# Sensors.net
KiCad netlist of a schematic drawn in Altium Designer
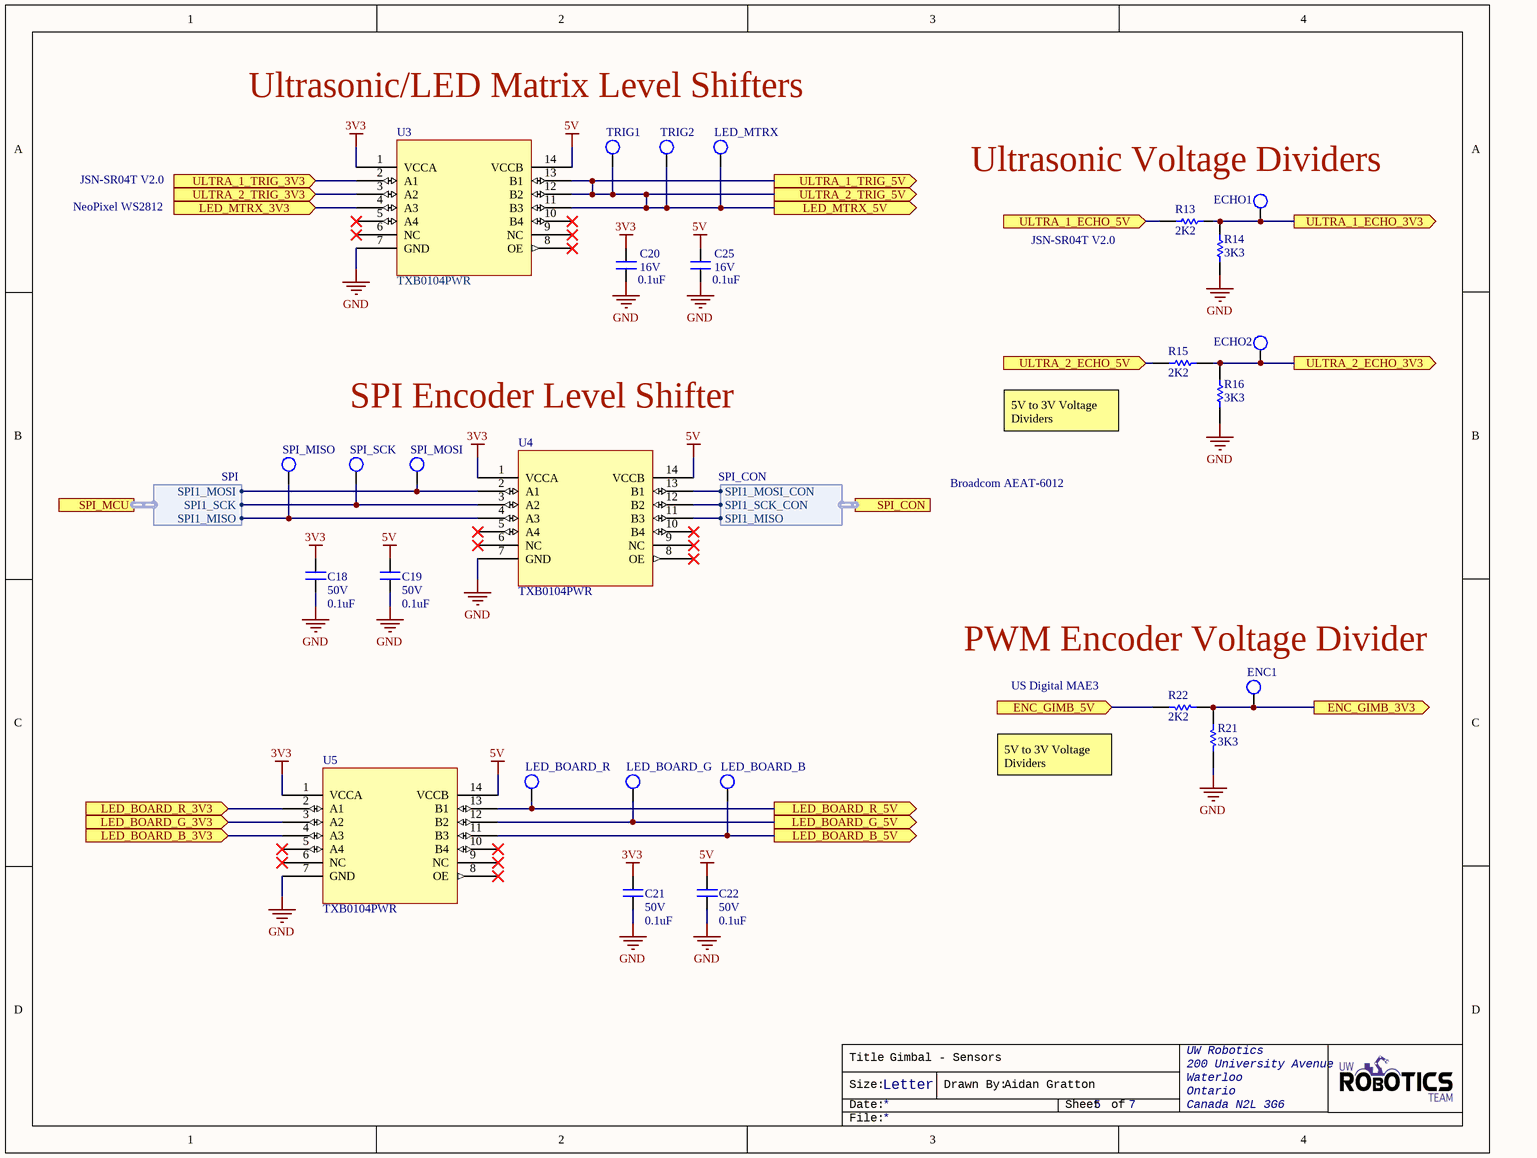
[diagram p0: Sensors.SchDoc]

(export (version "E")
  (design (tool "Eeschema 10.0.6"))
  (components
    (comp (ref "C18")
      (value "0.1uF")
      (footprint "CAPC0603(1608)55_N")
      (description "CAP CER 0.1UF 50V X7R 0603")
      (fields
        (field (name "MPN") "CC0603KRX7R9BB104")
        (field (name "MANUFACTURER") "Yageo")
        (field (name "VOLTAGE RATING") "50V")
      )
      (libsource (lib "UWRT_Schematic_Library_2020") (part "CAP_0.1uF_50V_0603"))
    )
    (comp (ref "C19")
      (value "0.1uF")
      (footprint "CAPC0603(1608)55_N")
      (description "CAP CER 0.1UF 50V X7R 0603")
      (fields
        (field (name "MPN") "CC0603KRX7R9BB104")
        (field (name "MANUFACTURER") "Yageo")
        (field (name "VOLTAGE RATING") "50V")
      )
      (libsource (lib "UWRT_Schematic_Library_2020") (part "CAP_0.1uF_50V_0603"))
    )
    (comp (ref "C20")
      (value "0.1uF")
      (footprint "CAPC0603(1608)55_N")
      (description "CAP CER 0.1UF 16V X7R 0603")
      (fields (field (name "VOLTAGE RATING") "16V") (field (name "Comment") "CAP_0.1uF_16V_0603"))
      (libsource (lib "UWRT_Schematic_Library_2020") (part "CAP_0.1uF_16V_0603"))
    )
    (comp (ref "C21")
      (value "0.1uF")
      (footprint "CAPC0603(1608)55_N")
      (description "CAP CER 0.1UF 50V X7R 0603")
      (fields
        (field (name "MPN") "CC0603KRX7R9BB104")
        (field (name "MANUFACTURER") "Yageo")
        (field (name "VOLTAGE RATING") "50V")
      )
      (libsource (lib "UWRT_Schematic_Library_2020") (part "CAP_0.1uF_50V_0603"))
    )
    (comp (ref "C22")
      (value "0.1uF")
      (footprint "CAPC0603(1608)55_N")
      (description "CAP CER 0.1UF 50V X7R 0603")
      (fields
        (field (name "MPN") "CC0603KRX7R9BB104")
        (field (name "MANUFACTURER") "Yageo")
        (field (name "VOLTAGE RATING") "50V")
      )
      (libsource (lib "UWRT_Schematic_Library_2020") (part "CAP_0.1uF_50V_0603"))
    )
    (comp (ref "C25")
      (value "0.1uF")
      (footprint "CAPC0603(1608)55_N")
      (description "CAP CER 0.1UF 16V X7R 0603")
      (fields (field (name "VOLTAGE RATING") "16V") (field (name "Comment") "CAP_0.1uF_16V_0603"))
      (libsource (lib "UWRT_Schematic_Library_2020") (part "CAP_0.1uF_16V_0603"))
    )
    (comp (ref "ECHO1")
      (value "TESTPOINT_LOOP")
      (footprint "TESTPOINT_LOOP")
      (description "Loop testpoint through-hole pad")
      (fields (field (name "MANUFACTURER") "Keystone Electronics"))
      (libsource (lib "UWRT_Schematic_Library_2020") (part "TESTPOINT_LOOP"))
    )
    (comp (ref "ECHO2")
      (value "TESTPOINT_LOOP")
      (footprint "TESTPOINT_LOOP")
      (description "Loop testpoint through-hole pad")
      (fields (field (name "MANUFACTURER") "Keystone Electronics"))
      (libsource (lib "UWRT_Schematic_Library_2020") (part "TESTPOINT_LOOP"))
    )
    (comp (ref "ENC1")
      (value "TESTPOINT_LOOP")
      (footprint "TESTPOINT_LOOP")
      (description "Loop testpoint through-hole pad")
      (fields (field (name "MANUFACTURER") "Keystone Electronics"))
      (libsource (lib "UWRT_Schematic_Library_2020") (part "TESTPOINT_LOOP"))
    )
    (comp (ref "LED_BOARD_B")
      (value "TESTPOINT_LOOP")
      (footprint "TESTPOINT_LOOP")
      (description "Loop testpoint through-hole pad")
      (fields (field (name "MANUFACTURER") "Keystone Electronics"))
      (libsource (lib "UWRT_Schematic_Library_2020") (part "TESTPOINT_LOOP"))
    )
    (comp (ref "LED_BOARD_G")
      (value "TESTPOINT_LOOP")
      (footprint "TESTPOINT_LOOP")
      (description "Loop testpoint through-hole pad")
      (fields (field (name "MANUFACTURER") "Keystone Electronics"))
      (libsource (lib "UWRT_Schematic_Library_2020") (part "TESTPOINT_LOOP"))
    )
    (comp (ref "LED_BOARD_R")
      (value "TESTPOINT_LOOP")
      (footprint "TESTPOINT_LOOP")
      (description "Loop testpoint through-hole pad")
      (fields (field (name "MANUFACTURER") "Keystone Electronics"))
      (libsource (lib "UWRT_Schematic_Library_2020") (part "TESTPOINT_LOOP"))
    )
    (comp (ref "LED_MTRX")
      (value "TESTPOINT_LOOP")
      (footprint "TESTPOINT_LOOP")
      (description "Loop testpoint through-hole pad")
      (libsource (lib "UWRT_Schematic_Library_2020") (part "TESTPOINT_LOOP"))
    )
    (comp (ref "R13")
      (value "2K2")
      (footprint "RESC0603(1608)_N")
      (description "RES SMD 2.2K OHM 1% 1/10W 0603")
      (fields (field (name "MANUFACTURER") "Yageo") (field (name "TOLERANCE") "1%"))
      (libsource (lib "UWRT_Schematic_Library_2020") (part "RES_2K2_0603"))
    )
    (comp (ref "R14")
      (value "3K3")
      (footprint "RESC0603(1608)_N")
      (description "RES SMD 3.3K OHM 5% 1/10W 0603")
      (fields (field (name "TOLERANCE") "5%") (field (name "DIGIKEY PART NUMBER") "311-3.3KGRCT-ND"))
      (libsource (lib "") (part "RES_3K3_0603_1"))
    )
    (comp (ref "R15")
      (value "2K2")
      (footprint "RESC0603(1608)_N")
      (description "RES SMD 2.2K OHM 1% 1/10W 0603")
      (fields (field (name "MANUFACTURER") "Yageo") (field (name "TOLERANCE") "1%"))
      (libsource (lib "UWRT_Schematic_Library_2020") (part "RES_2K2_0603"))
    )
    (comp (ref "R16")
      (value "3K3")
      (footprint "RESC0603(1608)_N")
      (description "RES SMD 3.3K OHM 5% 1/10W 0603")
      (fields (field (name "MANUFACTURER") "Yageo") (field (name "TOLERANCE") "5%"))
      (libsource (lib "UWRT_Schematic_Library_2020") (part "RES_3K3_0603"))
    )
    (comp (ref "R21")
      (value "3K3")
      (footprint "RESC0603(1608)_N")
      (description "RES SMD 3.3K OHM 5% 1/10W 0603")
      (fields (field (name "MANUFACTURER") "Yageo") (field (name "TOLERANCE") "5%"))
      (libsource (lib "UWRT_Schematic_Library_2020") (part "RES_3K3_0603"))
    )
    (comp (ref "R22")
      (value "2K2")
      (footprint "RESC0603(1608)_N")
      (description "RES SMD 2.2K OHM 1% 1/10W 0603")
      (fields (field (name "MANUFACTURER") "Yageo") (field (name "TOLERANCE") "1%"))
      (libsource (lib "UWRT_Schematic_Library_2020") (part "RES_2K2_0603"))
    )
    (comp (ref "SPI_MISO")
      (value "TESTPOINT_LOOP")
      (footprint "TESTPOINT_LOOP")
      (description "Loop testpoint through-hole pad")
      (fields (field (name "MANUFACTURER") "Keystone Electronics"))
      (libsource (lib "UWRT_Schematic_Library_2020") (part "TESTPOINT_LOOP"))
    )
    (comp (ref "SPI_MOSI")
      (value "TESTPOINT_LOOP")
      (footprint "TESTPOINT_LOOP")
      (description "Loop testpoint through-hole pad")
      (fields (field (name "MANUFACTURER") "Keystone Electronics"))
      (libsource (lib "UWRT_Schematic_Library_2020") (part "TESTPOINT_LOOP"))
    )
    (comp (ref "SPI_SCK")
      (value "TESTPOINT_LOOP")
      (footprint "TESTPOINT_LOOP")
      (description "Loop testpoint through-hole pad")
      (fields (field (name "MANUFACTURER") "Keystone Electronics"))
      (libsource (lib "UWRT_Schematic_Library_2020") (part "TESTPOINT_LOOP"))
    )
    (comp (ref "TRIG1")
      (value "TESTPOINT_LOOP")
      (footprint "TESTPOINT_LOOP")
      (description "Loop testpoint through-hole pad")
      (fields (field (name "MANUFACTURER") "Keystone Electronics"))
      (libsource (lib "UWRT_Schematic_Library_2020") (part "TESTPOINT_LOOP"))
    )
    (comp (ref "TRIG2")
      (value "TESTPOINT_LOOP")
      (footprint "TESTPOINT_LOOP")
      (description "Loop testpoint through-hole pad")
      (fields (field (name "MANUFACTURER") "Keystone Electronics"))
      (libsource (lib "UWRT_Schematic_Library_2020") (part "TESTPOINT_LOOP"))
    )
    (comp (ref "U3")
      (value "TXB0104PWR")
      (footprint "UWRT_Footprint_Library_2020:PW14")
      (fields
        (field (name "MANUFACTURER_PART_NUMBER") "TXB0104PWR")
        (field (name "GENERIC_PART_NUMBER") "TXB0104")
        (field (name "MANUFACTURER") "Texas Instruments")
      )
      (libsource (lib "UWRT_Schematic_Library_2020") (part "IC_4CH_LVL_SHIFTER"))
    )
    (comp (ref "U4")
      (value "TXB0104PWR")
      (footprint "UWRT_Footprint_Library_2020:PW14")
      (fields
        (field (name "GENERIC_PART_NUMBER") "TXB0104")
        (field (name "MANUFACTURER") "Texas Instruments")
      )
      (libsource (lib "UWRT_Schematic_Library_2020") (part "IC_4CH_LVL_SHIFTER"))
    )
    (comp (ref "U5")
      (value "TXB0104PWR")
      (footprint "UWRT_Footprint_Library_2020:PW14")
      (fields
        (field (name "GENERIC_PART_NUMBER") "TXB0104")
        (field (name "MANUFACTURER") "Texas Instruments")
      )
      (libsource (lib "UWRT_Schematic_Library_2020") (part "IC_4CH_LVL_SHIFTER"))
    )
  )
  (nets
    (net (code "3") (name "/ENC_GIMB_3V3") (class "Default")
      (node (ref "ENC1") (pin "1") (pintype "passive"))
      (node (ref "R21") (pin "1") (pinfunction "1_1") (pintype "passive"))
      (node (ref "R22") (pin "1") (pinfunction "1_1") (pintype "passive"))
    )
    (net (code "4") (name "/ENC_GIMB_5V") (class "Default")
      (node (ref "R22") (pin "2") (pinfunction "2_2") (pintype "passive"))
    )
    (net (code "5") (name "/LED_BOARD_B_3V3") (class "Default")
      (node (ref "U5") (pin "4") (pinfunction "A3_4") (pintype "bidirectional"))
    )
    (net (code "6") (name "/LED_BOARD_B_5V") (class "Default")
      (node (ref "LED_BOARD_B") (pin "1") (pintype "passive"))
      (node (ref "U5") (pin "11") (pinfunction "B3_11") (pintype "bidirectional"))
    )
    (net (code "7") (name "/LED_BOARD_G_3V3") (class "Default")
      (node (ref "U5") (pin "3") (pinfunction "A2_3") (pintype "bidirectional"))
    )
    (net (code "8") (name "/LED_BOARD_G_5V") (class "Default")
      (node (ref "LED_BOARD_G") (pin "1") (pintype "passive"))
      (node (ref "U5") (pin "12") (pinfunction "B2_12") (pintype "bidirectional"))
    )
    (net (code "9") (name "/LED_BOARD_R_3V3") (class "Default")
      (node (ref "U5") (pin "2") (pinfunction "A1_2") (pintype "bidirectional"))
    )
    (net (code "10") (name "/LED_BOARD_R_5V") (class "Default")
      (node (ref "LED_BOARD_R") (pin "1") (pintype "passive"))
      (node (ref "U5") (pin "13") (pinfunction "B1_13") (pintype "bidirectional"))
    )
    (net (code "11") (name "/LED_MTRX_3V3") (class "Default")
      (node (ref "U3") (pin "4") (pinfunction "A3_4") (pintype "bidirectional"))
    )
    (net (code "12") (name "/LED_MTRX_5V") (class "Default")
      (node (ref "LED_MTRX") (pin "1") (pintype "passive"))
      (node (ref "TRIG1") (pin "1") (pintype "passive"))
      (node (ref "TRIG2") (pin "1") (pintype "passive"))
      (node (ref "U3") (pin "11") (pinfunction "B3_11") (pintype "bidirectional"))
      (node (ref "U3") (pin "12") (pinfunction "B2_12") (pintype "bidirectional"))
      (node (ref "U3") (pin "13") (pinfunction "B1_13") (pintype "bidirectional"))
    )
    (net (code "13") (name "/SPI1_MOSI") (class "Default")
      (node (ref "SPI_MOSI") (pin "1") (pintype "passive"))
      (node (ref "U4") (pin "2") (pinfunction "A1_2") (pintype "bidirectional"))
    )
    (net (code "14") (name "/SPI1_MOSI_CON") (class "Default")
      (node (ref "U4") (pin "13") (pinfunction "B1_13") (pintype "bidirectional"))
    )
    (net (code "15") (name "/SPI1_SCK") (class "Default")
      (node (ref "SPI_SCK") (pin "1") (pintype "passive"))
      (node (ref "U4") (pin "3") (pinfunction "A2_3") (pintype "bidirectional"))
    )
    (net (code "16") (name "/SPI1_SCK_CON") (class "Default")
      (node (ref "U4") (pin "12") (pinfunction "B2_12") (pintype "bidirectional"))
    )
    (net (code "17") (name "/ULTRA_1_ECHO_3V3") (class "Default")
      (node (ref "ECHO1") (pin "1") (pintype "passive"))
      (node (ref "R13") (pin "1") (pinfunction "1_1") (pintype "passive"))
      (node (ref "R14") (pin "2") (pinfunction "2_2") (pintype "passive"))
    )
    (net (code "18") (name "/ULTRA_1_ECHO_5V") (class "Default")
      (node (ref "R13") (pin "2") (pinfunction "2_2") (pintype "passive"))
    )
    (net (code "19") (name "/ULTRA_1_TRIG_3V3") (class "Default")
      (node (ref "U3") (pin "2") (pinfunction "A1_2") (pintype "bidirectional"))
    )
    (net (code "20") (name "/ULTRA_2_ECHO_3V3") (class "Default")
      (node (ref "ECHO2") (pin "1") (pintype "passive"))
      (node (ref "R15") (pin "1") (pinfunction "1_1") (pintype "passive"))
      (node (ref "R16") (pin "1") (pinfunction "1_1") (pintype "passive"))
    )
    (net (code "21") (name "/ULTRA_2_ECHO_5V") (class "Default")
      (node (ref "R15") (pin "2") (pinfunction "2_2") (pintype "passive"))
    )
    (net (code "22") (name "/ULTRA_2_TRIG_3V3") (class "Default")
      (node (ref "U3") (pin "3") (pinfunction "A2_3") (pintype "bidirectional"))
    )
    (net (code "25") (name "3V3") (class "Default")
      (node (ref "C18") (pin "2") (pinfunction "2_2") (pintype "passive"))
      (node (ref "C20") (pin "2") (pinfunction "2_2") (pintype "passive"))
      (node (ref "C21") (pin "2") (pinfunction "2_2") (pintype "passive"))
      (node (ref "U3") (pin "1") (pinfunction "VCCA_1") (pintype "power_in"))
      (node (ref "U4") (pin "1") (pinfunction "VCCA_1") (pintype "power_in"))
      (node (ref "U5") (pin "1") (pinfunction "VCCA_1") (pintype "power_in"))
    )
    (net (code "26") (name "5V") (class "Default")
      (node (ref "C19") (pin "2") (pinfunction "2_2") (pintype "passive"))
      (node (ref "C22") (pin "2") (pinfunction "2_2") (pintype "passive"))
      (node (ref "C25") (pin "2") (pinfunction "2_2") (pintype "passive"))
      (node (ref "U3") (pin "14") (pinfunction "VCCB_14") (pintype "power_in"))
      (node (ref "U4") (pin "14") (pinfunction "VCCB_14") (pintype "power_in"))
      (node (ref "U5") (pin "14") (pinfunction "VCCB_14") (pintype "power_in"))
    )
    (net (code "27") (name "GND") (class "Default")
      (node (ref "C18") (pin "1") (pinfunction "1_1") (pintype "passive"))
      (node (ref "C19") (pin "1") (pinfunction "1_1") (pintype "passive"))
      (node (ref "C20") (pin "1") (pinfunction "1_1") (pintype "passive"))
      (node (ref "C21") (pin "1") (pinfunction "1_1") (pintype "passive"))
      (node (ref "C22") (pin "1") (pinfunction "1_1") (pintype "passive"))
      (node (ref "C25") (pin "1") (pinfunction "1_1") (pintype "passive"))
      (node (ref "R14") (pin "1") (pinfunction "1_1") (pintype "passive"))
      (node (ref "R16") (pin "2") (pinfunction "2_2") (pintype "passive"))
      (node (ref "R21") (pin "2") (pinfunction "2_2") (pintype "passive"))
      (node (ref "U3") (pin "7") (pinfunction "GND_7") (pintype "power_in"))
      (node (ref "U4") (pin "7") (pinfunction "GND_7") (pintype "power_in"))
      (node (ref "U5") (pin "7") (pinfunction "GND_7") (pintype "power_in"))
    )
    (net (code "28") (name "Net-(U4-A3)") (class "Default")
      (node (ref "SPI_MISO") (pin "1") (pintype "passive"))
      (node (ref "U4") (pin "4") (pinfunction "A3_4") (pintype "bidirectional"))
    )
    (net (code "29") (name "unconnected-(U3-A4-Pad5)") (class "Default")
      (node (ref "U3") (pin "5") (pinfunction "A4_5") (pintype "bidirectional+no_connect"))
    )
    (net (code "30") (name "unconnected-(U3-B4-Pad10)") (class "Default")
      (node (ref "U3") (pin "10") (pinfunction "B4_10") (pintype "bidirectional+no_connect"))
    )
    (net (code "31") (name "unconnected-(U3-NC-Pad6)") (class "Default")
      (node (ref "U3") (pin "6") (pinfunction "NC_6") (pintype "passive+no_connect"))
    )
    (net (code "32") (name "unconnected-(U3-NC-Pad9)") (class "Default")
      (node (ref "U3") (pin "9") (pinfunction "NC_9") (pintype "passive+no_connect"))
    )
    (net (code "33") (name "unconnected-(U3-OE-Pad8)") (class "Default")
      (node (ref "U3") (pin "8") (pinfunction "OE_8") (pintype "output+no_connect"))
    )
    (net (code "34") (name "unconnected-(U4-A4-Pad5)") (class "Default")
      (node (ref "U4") (pin "5") (pinfunction "A4_5") (pintype "bidirectional+no_connect"))
    )
    (net (code "35") (name "unconnected-(U4-B3-Pad11)") (class "Default")
      (node (ref "U4") (pin "11") (pinfunction "B3_11") (pintype "bidirectional"))
    )
    (net (code "36") (name "unconnected-(U4-B4-Pad10)") (class "Default")
      (node (ref "U4") (pin "10") (pinfunction "B4_10") (pintype "bidirectional+no_connect"))
    )
    (net (code "37") (name "unconnected-(U4-NC-Pad6)") (class "Default")
      (node (ref "U4") (pin "6") (pinfunction "NC_6") (pintype "passive+no_connect"))
    )
    (net (code "38") (name "unconnected-(U4-NC-Pad9)") (class "Default")
      (node (ref "U4") (pin "9") (pinfunction "NC_9") (pintype "passive+no_connect"))
    )
    (net (code "39") (name "unconnected-(U4-OE-Pad8)") (class "Default")
      (node (ref "U4") (pin "8") (pinfunction "OE_8") (pintype "output+no_connect"))
    )
    (net (code "40") (name "unconnected-(U5-A4-Pad5)") (class "Default")
      (node (ref "U5") (pin "5") (pinfunction "A4_5") (pintype "bidirectional+no_connect"))
    )
    (net (code "41") (name "unconnected-(U5-B4-Pad10)") (class "Default")
      (node (ref "U5") (pin "10") (pinfunction "B4_10") (pintype "bidirectional+no_connect"))
    )
    (net (code "42") (name "unconnected-(U5-NC-Pad6)") (class "Default")
      (node (ref "U5") (pin "6") (pinfunction "NC_6") (pintype "passive+no_connect"))
    )
    (net (code "43") (name "unconnected-(U5-NC-Pad9)") (class "Default")
      (node (ref "U5") (pin "9") (pinfunction "NC_9") (pintype "passive+no_connect"))
    )
    (net (code "44") (name "unconnected-(U5-OE-Pad8)") (class "Default")
      (node (ref "U5") (pin "8") (pinfunction "OE_8") (pintype "output+no_connect"))
    )
  )
)
